# Fonte.net
KiCad netlist of a schematic drawn in EAGLE
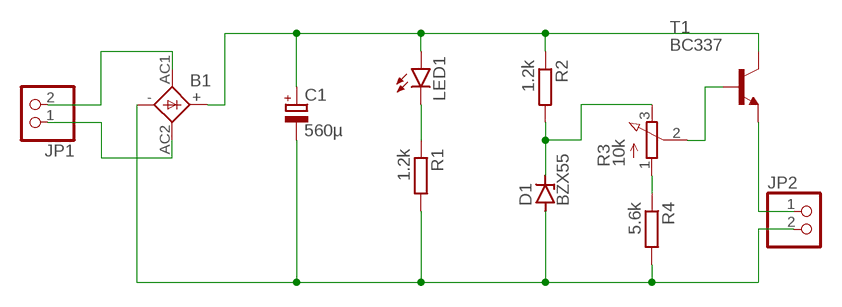
[diagram p0: schematic, sheet 1]

(export (version "E")
  (design (tool "Eeschema 10.0.6"))
  (components
    (comp (ref "B1")
      (value "2KBB-R")
      (footprint "eagle-import:2KBB-R")
      (libsource (lib "eagle-import") (part "2KBB-R"))
    )
    (comp (ref "C1")
      (value "560µ")
      (footprint "eagle-import:E3,5-10")
      (libsource (lib "eagle-import") (part "CPOL-EUE3.5-10"))
    )
    (comp (ref "D1")
      (value "BZX55")
      (footprint "eagle-import:DO35Z10")
      (libsource (lib "eagle-import") (part "BZX55"))
    )
    (comp (ref "JP1")
      (value "PINHD-1X2")
      (footprint "eagle-import:1X02")
      (libsource (lib "eagle-import") (part "PINHD-1X2"))
    )
    (comp (ref "JP2")
      (value "PINHD-1X2")
      (footprint "eagle-import:1X02")
      (libsource (lib "eagle-import") (part "PINHD-1X2"))
    )
    (comp (ref "LED1")
      (value "LED5MM")
      (footprint "eagle-import:LED5MM")
      (libsource (lib "eagle-import") (part "LED5MM"))
    )
    (comp (ref "R1")
      (value "1.2k")
      (footprint "eagle-import:0204_7")
      (libsource (lib "eagle-import") (part "R-EU_0204/7"))
    )
    (comp (ref "R2")
      (value "1.2k")
      (footprint "eagle-import:0204_7")
      (libsource (lib "eagle-import") (part "R-EU_0204/7"))
    )
    (comp (ref "R3")
      (value "10k")
      (footprint "eagle-import:3RP_1610N")
      (libsource (lib "eagle-import") (part "3RP/1610N"))
    )
    (comp (ref "R4")
      (value "5.6k")
      (footprint "eagle-import:0204_7")
      (libsource (lib "eagle-import") (part "R-EU_0204/7"))
    )
    (comp (ref "T1")
      (value "BC337")
      (footprint "eagle-import:TO92")
      (libsource (lib "eagle-import") (part "BC337"))
    )
  )
  (nets
    (net (code "1") (name "Net-(B1-Pad-)") (class "Default")
      (node (ref "B1") (pin "-") (pinfunction "-_-") (pintype "passive"))
      (node (ref "C1") (pin "-") (pinfunction "-_-") (pintype "passive"))
      (node (ref "D1") (pin "A") (pinfunction "A_A") (pintype "passive"))
      (node (ref "JP2") (pin "2") (pinfunction "2_2") (pintype "passive"))
      (node (ref "R1") (pin "2") (pinfunction "2_2") (pintype "passive"))
      (node (ref "R4") (pin "2") (pinfunction "2_2") (pintype "passive"))
    )
    (net (code "2") (name "Net-(B1-PadAC1)") (class "Default")
      (node (ref "B1") (pin "AC1") (pinfunction "AC1_AC1") (pintype "passive"))
      (node (ref "JP1") (pin "2") (pinfunction "2_2") (pintype "passive"))
    )
    (net (code "3") (name "Net-(B1-PadAC2)") (class "Default")
      (node (ref "B1") (pin "AC2") (pinfunction "AC2_AC2") (pintype "passive"))
      (node (ref "JP1") (pin "1") (pinfunction "1_1") (pintype "passive"))
    )
    (net (code "4") (name "Net-(LED1-C)") (class "Default")
      (node (ref "LED1") (pin "K") (pinfunction "C_K") (pintype "passive"))
      (node (ref "R1") (pin "1") (pinfunction "1_1") (pintype "passive"))
    )
    (net (code "5") (name "Net-(R3-A)") (class "Default")
      (node (ref "R3") (pin "1") (pinfunction "A_1") (pintype "passive"))
      (node (ref "R4") (pin "1") (pinfunction "1_1") (pintype "passive"))
    )
    (net (code "6") (name "Net-(R3-E)") (class "Default")
      (node (ref "D1") (pin "C") (pinfunction "C_C") (pintype "passive"))
      (node (ref "R2") (pin "2") (pinfunction "2_2") (pintype "passive"))
      (node (ref "R3") (pin "3") (pinfunction "E_3") (pintype "passive"))
    )
    (net (code "7") (name "Net-(R3-S)") (class "Default")
      (node (ref "R3") (pin "2") (pinfunction "S_2") (pintype "passive"))
      (node (ref "T1") (pin "2") (pinfunction "B_2") (pintype "passive"))
    )
    (net (code "8") (name "Net-(T1-C)") (class "Default")
      (node (ref "B1") (pin "+") (pinfunction "+_+") (pintype "passive"))
      (node (ref "C1") (pin "+") (pinfunction "+_+") (pintype "passive"))
      (node (ref "LED1") (pin "A") (pinfunction "A_A") (pintype "passive"))
      (node (ref "R2") (pin "1") (pinfunction "1_1") (pintype "passive"))
      (node (ref "T1") (pin "3") (pinfunction "C_3") (pintype "passive"))
    )
    (net (code "9") (name "Net-(T1-E)") (class "Default")
      (node (ref "JP2") (pin "1") (pinfunction "1_1") (pintype "passive"))
      (node (ref "T1") (pin "1") (pinfunction "E_1") (pintype "passive"))
    )
  )
)
